# MezzanineDCDC_Overall.net
KiCad netlist of a schematic drawn in Altium Designer
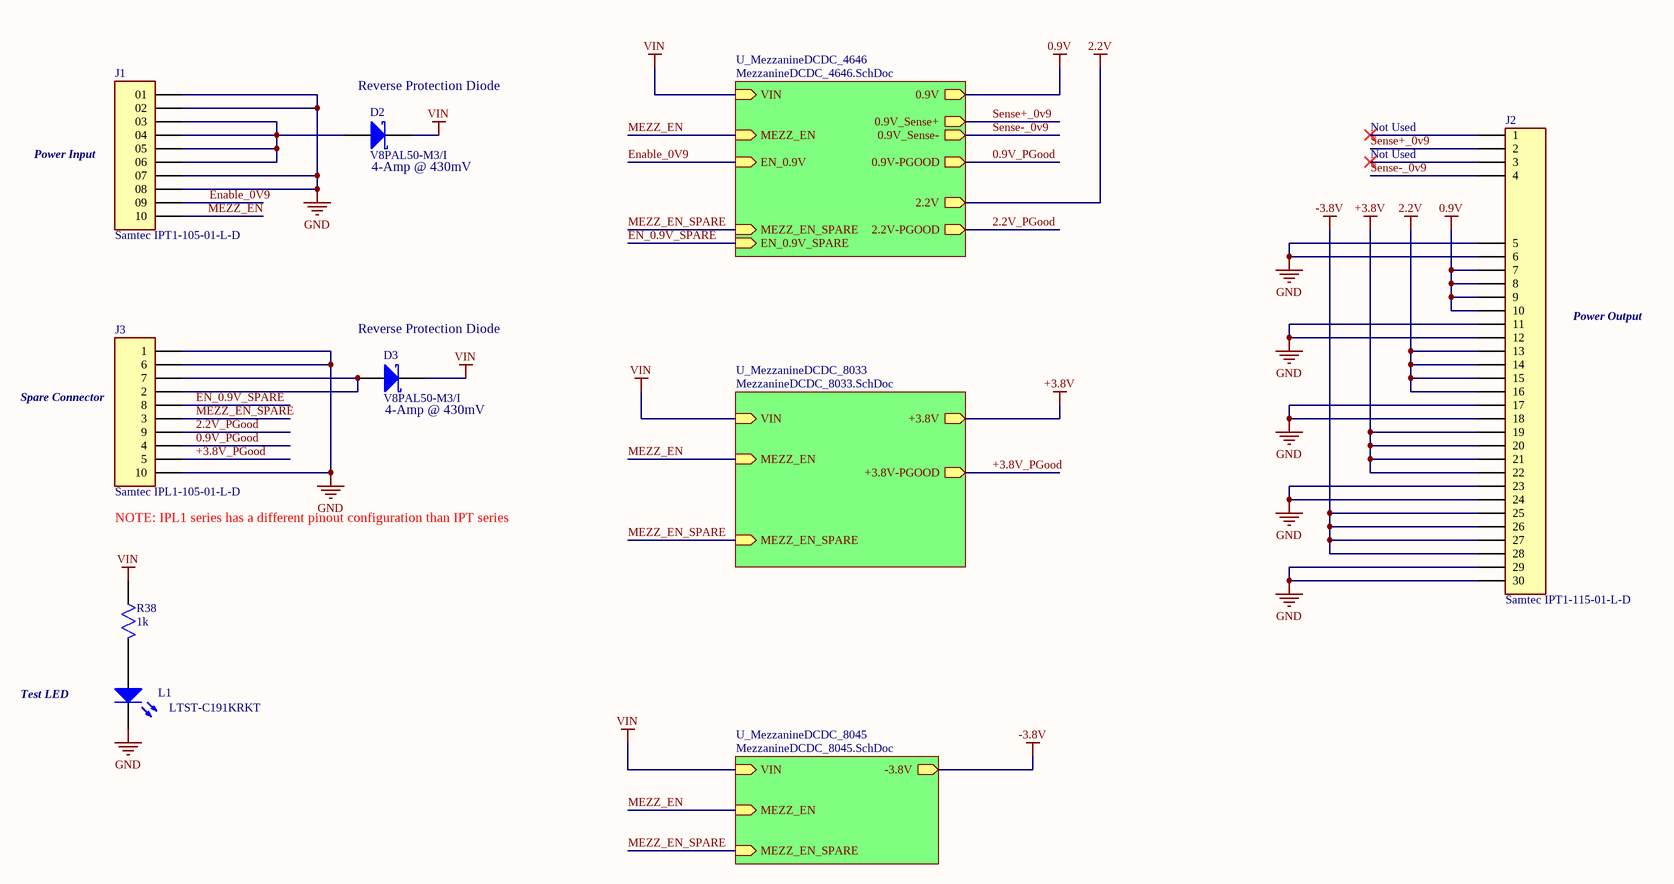
[diagram p0: MezzanineDCDC_Overall.SchDoc]

(export (version "E")
  (design (tool "Eeschema 10.0.6"))
  (components
    (comp (ref "D2")
      (value "V8PAL50-M3/I")
      (footprint "Schottky Diode V8PAL50-M3/I")
      (description "Diode Schottky 50V 4A Surface Mount DO-221BC (SMPA)")
      (libsource (lib "MezzanineDCDC") (part "Schotkky Diode"))
    )
    (comp (ref "D3")
      (value "V8PAL50-M3/I")
      (footprint "Schottky Diode V8PAL50-M3/I")
      (description "Diode Schottky 50V 4A Surface Mount DO-221BC (SMPA)")
      (libsource (lib "MezzanineDCDC") (part "Schotkky Diode"))
    )
    (comp (ref "J1")
      (value "Samtec IPT1-105-01-L-D")
      (footprint "SAMTEC_IPT1-105-01-L-D")
      (description "CONN HEADER VERT 10POS 2.54MM")
      (libsource (lib "MezzanineDCDC") (part "Samtec IPT1-105-01-L-D"))
    )
    (comp (ref "J2")
      (value "Samtec IPT1-115-01-L-D")
      (footprint "IPT1-115-01-L-D")
      (description "15x2 Pin Connector CONN HEADER VERT 30POS 2.54MM")
      (libsource (lib "MezzanineDCDC") (part "Samtec IPT1-115-01-L-D"))
    )
    (comp (ref "J3")
      (value "Samtec IPL1-105-01-L-D")
      (footprint "IPL1-105-01-L-D")
      (description "5x2 Pin connector")
      (libsource (lib "MezzanineDCDC") (part "Samtec IPL1-105-01-L-D"))
    )
    (comp (ref "L1")
      (value "LTST-C191KRKT")
      (footprint "LED")
      (description "Red 631nm LED Indication - Discrete 2V 0603 (1608 Metric)")
      (libsource (lib "MezzanineDCDC") (part "LED"))
    )
    (comp (ref "R38")
      (value "1k")
      (footprint "Resistor ERJ2G/CRCW 0402")
      (description "RES SMD 1K OHM 5% 1/10W 0402")
      (fields (field (name "Comment") "ERJ-2GEJ102X"))
      (libsource (lib "MezzanineDCDC") (part "ERJ2G Resistor 0402"))
    )
  )
  (nets
    (net (code "1") (name "+3.8V") (class "Default")
      (node (ref "J2") (pin "19") (pinfunction "19_19") (pintype "passive"))
      (node (ref "J2") (pin "20") (pinfunction "20_20") (pintype "passive"))
      (node (ref "J2") (pin "21") (pinfunction "21_21") (pintype "passive"))
      (node (ref "J2") (pin "22") (pinfunction "22_22") (pintype "passive"))
    )
    (net (code "2") (name "-3.8V") (class "Default")
      (node (ref "J2") (pin "25") (pinfunction "25_25") (pintype "passive"))
      (node (ref "J2") (pin "26") (pinfunction "26_26") (pintype "passive"))
      (node (ref "J2") (pin "27") (pinfunction "27_27") (pintype "passive"))
      (node (ref "J2") (pin "28") (pinfunction "28_28") (pintype "passive"))
    )
    (net (code "3") (name "/+3.8V_PGood") (class "Default")
      (node (ref "J3") (pin "5") (pinfunction "5_5") (pintype "passive"))
    )
    (net (code "4") (name "/0.9V_PGood") (class "Default")
      (node (ref "J3") (pin "4") (pinfunction "4_4") (pintype "passive"))
    )
    (net (code "5") (name "/2.2V_PGood") (class "Default")
      (node (ref "J3") (pin "9") (pinfunction "9_9") (pintype "passive"))
    )
    (net (code "6") (name "/EN_0.9V_SPARE") (class "Default")
      (node (ref "J3") (pin "8") (pinfunction "8_8") (pintype "passive"))
    )
    (net (code "7") (name "/Enable_0V9") (class "Default")
      (node (ref "J1") (pin "09") (pinfunction "09_09") (pintype "passive"))
    )
    (net (code "8") (name "/MEZZ_EN") (class "Default")
      (node (ref "J1") (pin "10") (pinfunction "10_10") (pintype "passive"))
    )
    (net (code "9") (name "/MEZZ_EN_SPARE") (class "Default")
      (node (ref "J3") (pin "3") (pinfunction "3_3") (pintype "passive"))
    )
    (net (code "10") (name "/Sense+_0v9") (class "Default")
      (node (ref "J2") (pin "2") (pinfunction "2_2") (pintype "passive"))
    )
    (net (code "11") (name "/Sense-_0v9") (class "Default")
      (node (ref "J2") (pin "4") (pinfunction "4_4") (pintype "passive"))
    )
    (net (code "12") (name "0.9V") (class "Default")
      (node (ref "J2") (pin "10") (pinfunction "10_10") (pintype "passive"))
      (node (ref "J2") (pin "7") (pinfunction "7_7") (pintype "passive"))
      (node (ref "J2") (pin "8") (pinfunction "8_8") (pintype "passive"))
      (node (ref "J2") (pin "9") (pinfunction "9_9") (pintype "passive"))
    )
    (net (code "13") (name "2.2V") (class "Default")
      (node (ref "J2") (pin "13") (pinfunction "13_13") (pintype "passive"))
      (node (ref "J2") (pin "14") (pinfunction "14_14") (pintype "passive"))
      (node (ref "J2") (pin "15") (pinfunction "15_15") (pintype "passive"))
      (node (ref "J2") (pin "16") (pinfunction "16_16") (pintype "passive"))
    )
    (net (code "14") (name "GND") (class "Default")
      (node (ref "J1") (pin "01") (pinfunction "01_01") (pintype "passive"))
      (node (ref "J1") (pin "02") (pinfunction "02_02") (pintype "passive"))
      (node (ref "J1") (pin "07") (pinfunction "07_07") (pintype "passive"))
      (node (ref "J1") (pin "08") (pinfunction "08_08") (pintype "passive"))
      (node (ref "J2") (pin "11") (pinfunction "11_11") (pintype "passive"))
      (node (ref "J2") (pin "12") (pinfunction "12_12") (pintype "passive"))
      (node (ref "J2") (pin "17") (pinfunction "17_17") (pintype "passive"))
      (node (ref "J2") (pin "18") (pinfunction "18_18") (pintype "passive"))
      (node (ref "J2") (pin "23") (pinfunction "23_23") (pintype "passive"))
      (node (ref "J2") (pin "24") (pinfunction "24_24") (pintype "passive"))
      (node (ref "J2") (pin "29") (pinfunction "29_29") (pintype "passive"))
      (node (ref "J2") (pin "30") (pinfunction "30_30") (pintype "passive"))
      (node (ref "J2") (pin "5") (pinfunction "5_5") (pintype "passive"))
      (node (ref "J2") (pin "6") (pinfunction "6_6") (pintype "passive"))
      (node (ref "J3") (pin "1") (pinfunction "1_1") (pintype "passive"))
      (node (ref "J3") (pin "10") (pinfunction "10_10") (pintype "passive"))
      (node (ref "J3") (pin "6") (pinfunction "6_6") (pintype "passive"))
      (node (ref "L1") (pin "2") (pinfunction "K_2") (pintype "passive"))
    )
    (net (code "15") (name "Net-(D2-A)") (class "Default")
      (node (ref "D2") (pin "2") (pinfunction "A_2") (pintype "passive"))
      (node (ref "J1") (pin "03") (pinfunction "03_03") (pintype "passive"))
      (node (ref "J1") (pin "04") (pinfunction "04_04") (pintype "passive"))
      (node (ref "J1") (pin "05") (pinfunction "05_05") (pintype "passive"))
      (node (ref "J1") (pin "06") (pinfunction "06_06") (pintype "passive"))
    )
    (net (code "16") (name "Net-(D3-A)") (class "Default")
      (node (ref "D3") (pin "2") (pinfunction "A_2") (pintype "passive"))
      (node (ref "J3") (pin "2") (pinfunction "2_2") (pintype "passive"))
      (node (ref "J3") (pin "7") (pinfunction "7_7") (pintype "passive"))
    )
    (net (code "17") (name "Net-(L1-A)") (class "Default")
      (node (ref "L1") (pin "1") (pinfunction "A_1") (pintype "passive"))
      (node (ref "R38") (pin "2") (pinfunction "1_2") (pintype "passive"))
    )
    (net (code "18") (name "VIN") (class "Default")
      (node (ref "D2") (pin "1") (pinfunction "K_1") (pintype "passive"))
      (node (ref "D3") (pin "1") (pinfunction "K_1") (pintype "passive"))
      (node (ref "R38") (pin "1") (pinfunction "0_1") (pintype "passive"))
    )
    (net (code "19") (name "unconnected-(J2-Pad1)") (class "Default")
      (node (ref "J2") (pin "1") (pinfunction "1_1") (pintype "passive+no_connect"))
    )
    (net (code "20") (name "unconnected-(J2-Pad3)") (class "Default")
      (node (ref "J2") (pin "3") (pinfunction "3_3") (pintype "passive+no_connect"))
    )
  )
)
